# arduino_katakana_dictionary.net
KiCad netlist of a schematic drawn in EAGLE
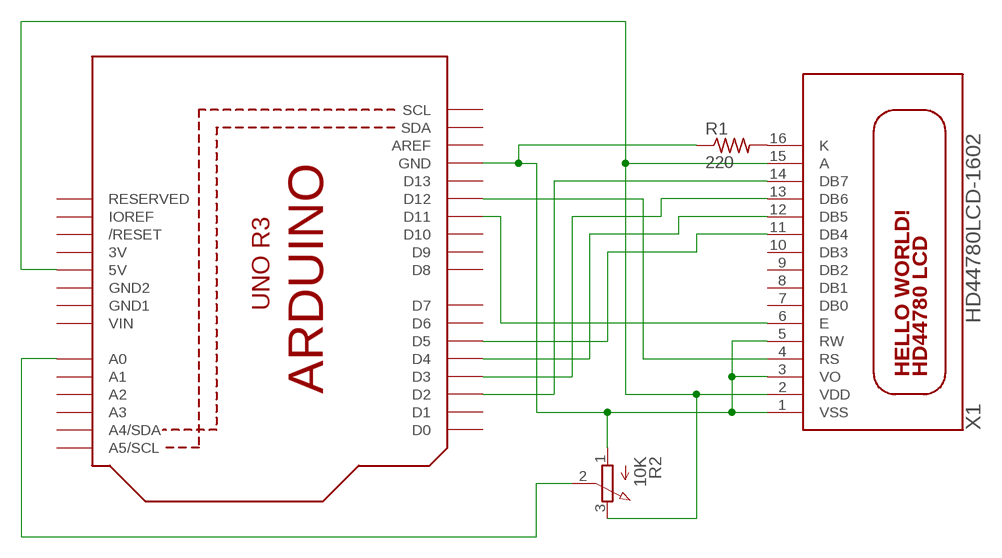
[diagram p0: schematic, sheet 1]

(export (version "E")
  (design (tool "Eeschema 10.0.6"))
  (components
    (comp (ref "R1")
      (value "220")
      (footprint "eagle-import:0204_5")
      (libsource (lib "eagle-import") (part "R-US_0204/5"))
    )
    (comp (ref "R2")
      (value "10K")
      (footprint "eagle-import:3RP_1610N")
      (libsource (lib "eagle-import") (part "3RP/1610N"))
    )
    (comp (ref "U1")
      (value "ARDUINOR3-DIMENSION")
      (footprint "eagle-import:ARDUINOR3")
      (libsource (lib "eagle-import") (part "ARDUINOR3-DIMENSION"))
    )
    (comp (ref "X1")
      (value "HD44780LCD-1602")
      (footprint "eagle-import:LCD1602")
      (libsource (lib "eagle-import") (part "HD44780LCD-1602"))
    )
  )
  (nets
    (net (code "1") (name "/3V") (class "Default")
      (node (ref "U1") (pin "3V") (pinfunction "3V_3V") (pintype "power_in"))
    )
    (net (code "2") (name "/GND1") (class "Default")
      (node (ref "U1") (pin "GND1") (pinfunction "GND1_GND1") (pintype "power_in"))
    )
    (net (code "3") (name "/GND2") (class "Default")
      (node (ref "U1") (pin "GND2") (pinfunction "GND2_GND2") (pintype "power_in"))
    )
    (net (code "4") (name "/VIN") (class "Default")
      (node (ref "U1") (pin "VIN") (pinfunction "VIN_VIN") (pintype "power_in"))
    )
    (net (code "5") (name "Net-(R2-A)") (class "Default")
      (node (ref "R1") (pin "1") (pinfunction "1_1") (pintype "passive"))
      (node (ref "R2") (pin "1") (pinfunction "A_1") (pintype "passive"))
      (node (ref "U1") (pin "GND") (pinfunction "GND_GND") (pintype "power_in"))
      (node (ref "X1") (pin "1") (pinfunction "VSS_1") (pintype "power_in"))
      (node (ref "X1") (pin "3") (pinfunction "VO_3") (pintype "input"))
      (node (ref "X1") (pin "5") (pinfunction "RW_5") (pintype "input"))
    )
    (net (code "6") (name "Net-(R2-E)") (class "Default")
      (node (ref "R2") (pin "3") (pinfunction "E_3") (pintype "passive"))
      (node (ref "U1") (pin "5V") (pinfunction "5V_5V") (pintype "power_in"))
      (node (ref "X1") (pin "15") (pinfunction "A_15") (pintype "input"))
      (node (ref "X1") (pin "2") (pinfunction "VDD_2") (pintype "power_in"))
    )
    (net (code "7") (name "Net-(R2-S)") (class "Default")
      (node (ref "R2") (pin "2") (pinfunction "S_2") (pintype "passive"))
      (node (ref "U1") (pin "A0") (pinfunction "A0_A0") (pintype "bidirectional"))
    )
    (net (code "8") (name "Net-(X1-DB4)") (class "Default")
      (node (ref "U1") (pin "D5") (pinfunction "D5_D5") (pintype "bidirectional"))
      (node (ref "X1") (pin "11") (pinfunction "DB4_11") (pintype "bidirectional"))
    )
    (net (code "9") (name "Net-(X1-DB5)") (class "Default")
      (node (ref "U1") (pin "D4") (pinfunction "D4_D4") (pintype "bidirectional"))
      (node (ref "X1") (pin "12") (pinfunction "DB5_12") (pintype "bidirectional"))
    )
    (net (code "10") (name "Net-(X1-DB6)") (class "Default")
      (node (ref "U1") (pin "D3") (pinfunction "D3_D3") (pintype "bidirectional"))
      (node (ref "X1") (pin "13") (pinfunction "DB6_13") (pintype "bidirectional"))
    )
    (net (code "11") (name "Net-(X1-DB7)") (class "Default")
      (node (ref "U1") (pin "D2") (pinfunction "D2_D2") (pintype "bidirectional"))
      (node (ref "X1") (pin "14") (pinfunction "DB7_14") (pintype "bidirectional"))
    )
    (net (code "12") (name "Net-(X1-E)") (class "Default")
      (node (ref "U1") (pin "D11") (pinfunction "D11_D11") (pintype "bidirectional"))
      (node (ref "X1") (pin "6") (pinfunction "E_6") (pintype "input"))
    )
    (net (code "13") (name "Net-(X1-K)") (class "Default")
      (node (ref "R1") (pin "2") (pinfunction "2_2") (pintype "passive"))
      (node (ref "X1") (pin "16") (pinfunction "K_16") (pintype "input"))
    )
    (net (code "14") (name "Net-(X1-RS)") (class "Default")
      (node (ref "U1") (pin "D12") (pinfunction "D12_D12") (pintype "bidirectional"))
      (node (ref "X1") (pin "4") (pinfunction "RS_4") (pintype "input"))
    )
    (net (code "15") (name "unconnected-(U1-A4{slash}SDA-PadA4)") (class "Default")
      (node (ref "U1") (pin "A4") (pinfunction "A4/SDA_A4") (pintype "bidirectional"))
    )
    (net (code "16") (name "unconnected-(U1-A5{slash}SCL-PadA5)") (class "Default")
      (node (ref "U1") (pin "A5") (pinfunction "A5/SCL_A5") (pintype "bidirectional"))
    )
    (net (code "17") (name "unconnected-(U1-PadA1)") (class "Default")
      (node (ref "U1") (pin "A1") (pinfunction "A1_A1") (pintype "bidirectional"))
    )
    (net (code "18") (name "unconnected-(U1-PadA2)") (class "Default")
      (node (ref "U1") (pin "A2") (pinfunction "A2_A2") (pintype "bidirectional"))
    )
    (net (code "19") (name "unconnected-(U1-PadA3)") (class "Default")
      (node (ref "U1") (pin "A3") (pinfunction "A3_A3") (pintype "bidirectional"))
    )
    (net (code "20") (name "unconnected-(U1-PadAREF)") (class "Default")
      (node (ref "U1") (pin "AREF") (pinfunction "AREF_AREF") (pintype "bidirectional"))
    )
    (net (code "21") (name "unconnected-(U1-PadD0)") (class "Default")
      (node (ref "U1") (pin "D0") (pinfunction "D0_D0") (pintype "bidirectional"))
    )
    (net (code "22") (name "unconnected-(U1-PadD1)") (class "Default")
      (node (ref "U1") (pin "D1") (pinfunction "D1_D1") (pintype "bidirectional"))
    )
    (net (code "23") (name "unconnected-(U1-PadD6)") (class "Default")
      (node (ref "U1") (pin "D6") (pinfunction "D6_D6") (pintype "bidirectional"))
    )
    (net (code "24") (name "unconnected-(U1-PadD7)") (class "Default")
      (node (ref "U1") (pin "D7") (pinfunction "D7_D7") (pintype "bidirectional"))
    )
    (net (code "25") (name "unconnected-(U1-PadD8)") (class "Default")
      (node (ref "U1") (pin "D8") (pinfunction "D8_D8") (pintype "bidirectional"))
    )
    (net (code "26") (name "unconnected-(U1-PadD9)") (class "Default")
      (node (ref "U1") (pin "D9") (pinfunction "D9_D9") (pintype "bidirectional"))
    )
    (net (code "27") (name "unconnected-(U1-PadD10)") (class "Default")
      (node (ref "U1") (pin "D10") (pinfunction "D10_D10") (pintype "bidirectional"))
    )
    (net (code "28") (name "unconnected-(U1-PadD13)") (class "Default")
      (node (ref "U1") (pin "D13") (pinfunction "D13_D13") (pintype "bidirectional"))
    )
    (net (code "29") (name "unconnected-(U1-PadIOREF)") (class "Default")
      (node (ref "U1") (pin "IOREF") (pinfunction "IOREF_IOREF") (pintype "output"))
    )
    (net (code "30") (name "unconnected-(U1-PadRESERVED)") (class "Default")
      (node (ref "U1") (pin "RESERVED") (pinfunction "RESERVED_RESERVED") (pintype "no_connect"))
    )
    (net (code "31") (name "unconnected-(U1-PadSCL)") (class "Default")
      (node (ref "U1") (pin "SCL") (pinfunction "SCL_SCL") (pintype "bidirectional"))
    )
    (net (code "32") (name "unconnected-(U1-PadSDA)") (class "Default")
      (node (ref "U1") (pin "SDA") (pinfunction "SDA_SDA") (pintype "bidirectional"))
    )
    (net (code "33") (name "unconnected-(U1-{slash}RESET-PadRESET)") (class "Default")
      (node (ref "U1") (pin "RESET") (pinfunction "/RESET_RESET") (pintype "bidirectional"))
    )
    (net (code "34") (name "unconnected-(X1-DB0-Pad7)") (class "Default")
      (node (ref "X1") (pin "7") (pinfunction "DB0_7") (pintype "bidirectional"))
    )
    (net (code "35") (name "unconnected-(X1-DB1-Pad8)") (class "Default")
      (node (ref "X1") (pin "8") (pinfunction "DB1_8") (pintype "bidirectional"))
    )
    (net (code "36") (name "unconnected-(X1-DB2-Pad9)") (class "Default")
      (node (ref "X1") (pin "9") (pinfunction "DB2_9") (pintype "bidirectional"))
    )
    (net (code "37") (name "unconnected-(X1-DB3-Pad10)") (class "Default")
      (node (ref "X1") (pin "10") (pinfunction "DB3_10") (pintype "bidirectional"))
    )
  )
)
